# FPSModule.net
KiCad netlist of a schematic drawn in Altium Designer
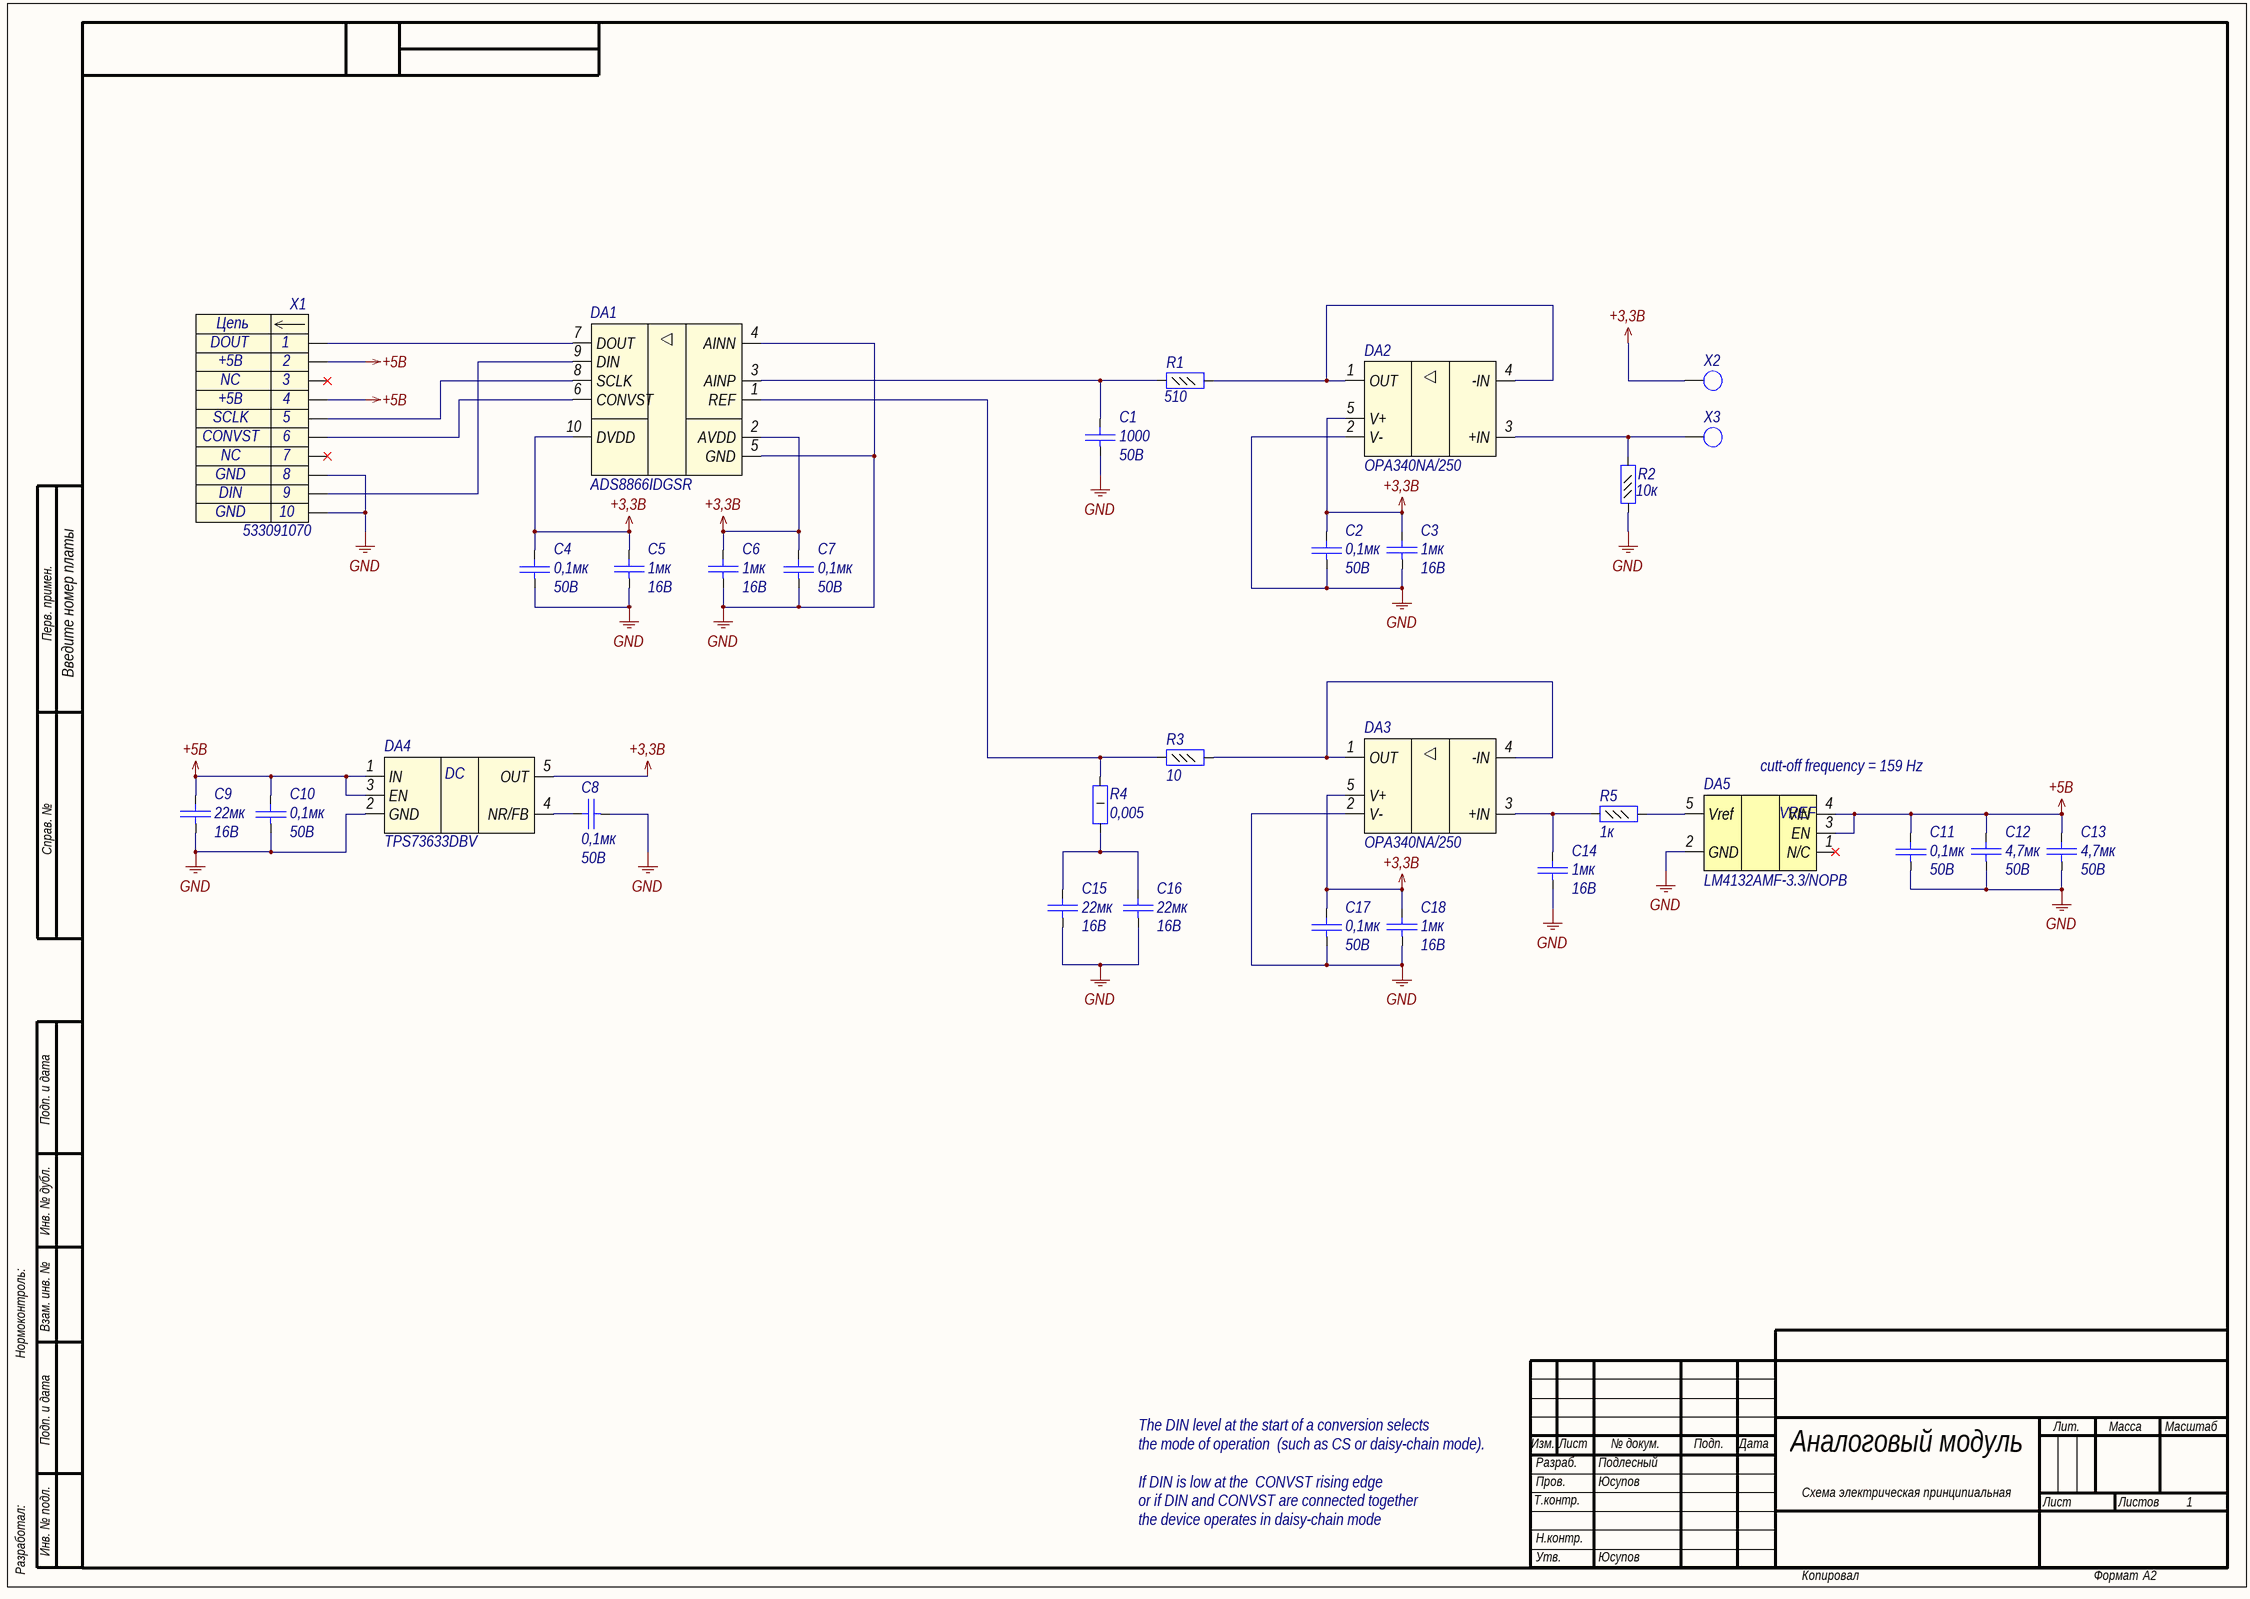
[diagram p0: FPSModule.SchDoc]

(export (version "E")
  (design (tool "Eeschema 10.0.6"))
  (components
    (comp (ref "C1")
      (value "1000")
      (footprint "C0402")
      (description "Конденсатор")
      (fields (field (name "VOLTAGE") "50B") (field (name "PART NUMBER") "GRM1555C1H102J"))
      (libsource (lib "MOP44") (part "Capacitor"))
    )
    (comp (ref "C2")
      (value "0,1мк")
      (footprint "C0402")
      (description "Конденсатор")
      (fields (field (name "VOLTAGE") "50В") (field (name "PART NUMBER") "GRM155R71H104KE14D "))
      (libsource (lib "MOP44") (part "Capacitor"))
    )
    (comp (ref "C3")
      (value "1мк")
      (footprint "C0603")
      (description "Конденсатор")
      (fields (field (name "VOLTAGE") "16B") (field (name "PART NUMBER") "GRM188R71C105KA12D**"))
      (libsource (lib "MOP44") (part "Capacitor"))
    )
    (comp (ref "C4")
      (value "0,1мк")
      (footprint "C0402")
      (description "Конденсатор")
      (fields (field (name "VOLTAGE") "50В") (field (name "PART NUMBER") "GRM155R71H104KE14D "))
      (libsource (lib "MOP44") (part "Capacitor"))
    )
    (comp (ref "C5")
      (value "1мк")
      (footprint "C0603")
      (description "Конденсатор")
      (fields (field (name "VOLTAGE") "16B") (field (name "PART NUMBER") "GRM188R71C105KA12D**"))
      (libsource (lib "MOP44") (part "Capacitor"))
    )
    (comp (ref "C6")
      (value "1мк")
      (footprint "C0603")
      (description "Конденсатор")
      (fields (field (name "VOLTAGE") "16B") (field (name "PART NUMBER") "GRM188R71C105KA12D**"))
      (libsource (lib "MOP44") (part "Capacitor"))
    )
    (comp (ref "C7")
      (value "0,1мк")
      (footprint "C0402")
      (description "Конденсатор")
      (fields (field (name "VOLTAGE") "50В") (field (name "PART NUMBER") "GRM155R71H104KE14D "))
      (libsource (lib "MOP44") (part "Capacitor"))
    )
    (comp (ref "C8")
      (value "0,1мк")
      (footprint "C0402")
      (description "Конденсатор")
      (fields (field (name "VOLTAGE") "50В") (field (name "PART NUMBER") "GRM155R71H104KE14D "))
      (libsource (lib "MOP44") (part "Capacitor"))
    )
    (comp (ref "C9")
      (value "22мк")
      (footprint "C1210")
      (description "Конденсатор")
      (fields (field (name "VOLTAGE") "16B") (field (name "PART NUMBER") "C3225X7R1C226M"))
      (libsource (lib "MOP44") (part "Capacitor"))
    )
    (comp (ref "C10")
      (value "0,1мк")
      (footprint "C0402")
      (description "Конденсатор")
      (fields (field (name "VOLTAGE") "50В") (field (name "PART NUMBER") "GRM155R71H104KE14D "))
      (libsource (lib "MOP44") (part "Capacitor"))
    )
    (comp (ref "C11")
      (value "0,1мк")
      (footprint "C0402")
      (description "Конденсатор")
      (fields (field (name "VOLTAGE") "50В") (field (name "PART NUMBER") "GRM155R71H104KE14D "))
      (libsource (lib "MOP44") (part "Capacitor"))
    )
    (comp (ref "C12")
      (value "4,7мк")
      (footprint "C0805")
      (description "Конденсатор")
      (fields (field (name "VOLTAGE") "50В") (field (name "PART NUMBER") "GRM21BZ71H475KE15L"))
      (libsource (lib "MOP44") (part "Capacitor"))
    )
    (comp (ref "C13")
      (value "4,7мк")
      (footprint "C0805")
      (description "Конденсатор")
      (fields (field (name "VOLTAGE") "50В") (field (name "PART NUMBER") "GRM21BZ71H475KE15L"))
      (libsource (lib "MOP44") (part "Capacitor"))
    )
    (comp (ref "C14")
      (value "1мк")
      (footprint "C0603")
      (description "Конденсатор")
      (fields (field (name "VOLTAGE") "16B") (field (name "PART NUMBER") "GRM188R71C105KA12D**"))
      (libsource (lib "MOP44") (part "Capacitor"))
    )
    (comp (ref "C15")
      (value "22мк")
      (footprint "C1210")
      (description "Конденсатор")
      (fields (field (name "VOLTAGE") "16B") (field (name "PART NUMBER") "C3225X7R1C226M"))
      (libsource (lib "MOP44") (part "Capacitor"))
    )
    (comp (ref "C16")
      (value "22мк")
      (footprint "C1210")
      (description "Конденсатор")
      (fields (field (name "VOLTAGE") "16B") (field (name "PART NUMBER") "C3225X7R1C226M"))
      (libsource (lib "MOP44") (part "Capacitor"))
    )
    (comp (ref "C17")
      (value "0,1мк")
      (footprint "C0402")
      (description "Конденсатор")
      (fields (field (name "VOLTAGE") "50В") (field (name "PART NUMBER") "GRM155R71H104KE14D "))
      (libsource (lib "MOP44") (part "Capacitor"))
    )
    (comp (ref "C18")
      (value "1мк")
      (footprint "C0603")
      (description "Конденсатор")
      (fields (field (name "VOLTAGE") "16B") (field (name "PART NUMBER") "GRM188R71C105KA12D**"))
      (libsource (lib "MOP44") (part "Capacitor"))
    )
    (comp (ref "DA1")
      (value "ADS8866")
      (footprint "MSOP10")
      (description "100-kSPS, serial interface, micropower, miniature,  single-ended input, SAR")
      (fields (field (name "PART NUMBER") "ADS8866IDGSR"))
      (libsource (lib "MOP44") (part "ADS8866"))
    )
    (comp (ref "DA2")
      (value "OPA340")
      (footprint "SOT23-5")
      (description "Operational Amplifiers\r\nMicroAmplifier")
      (fields (field (name "PART NUMBER") "OPA340NA/250"))
      (libsource (lib "MOP44") (part "OPA340"))
    )
    (comp (ref "DA3")
      (value "OPA340")
      (footprint "SOT23-5")
      (description "Operational Amplifiers\r\nMicroAmplifier")
      (fields (field (name "PART NUMBER") "OPA340NA/250"))
      (libsource (lib "MOP44") (part "OPA340"))
    )
    (comp (ref "DA4")
      (value "TPS736DBV")
      (footprint "SOT23-5")
      (description "400-mA Low-Dropout Regulator with Reverse Current  Protection")
      (fields (field (name "PART NUMBER") "TPS73633DBV") (field (name "MANUFACTURER") "Texas Instruments"))
      (libsource (lib "MOP44") (part "TPS736DBV"))
    )
    (comp (ref "DA5")
      (value "LM4132")
      (footprint "SOT23-5")
      (description "Precision Low Dropout Voltage Reference")
      (fields
        (field (name "PART NUMBER") "LM4132AMF-3.3/NOPB")
        (field (name "MANUFACTURER") "Texas Instruments")
      )
      (libsource (lib "MOP44") (part "LM4132"))
    )
    (comp (ref "R1")
      (value "510")
      (footprint "R0402")
      (description "Резистор")
      (fields (field (name "PART NUMBER") "RC0402FR-07510RL") (field (name "POWER") "0,062Вт"))
      (libsource (lib "MOP44") (part "Resistor_0,062Вт"))
    )
    (comp (ref "R2")
      (value "10к")
      (footprint "R0402")
      (description "Резистор")
      (fields (field (name "PART NUMBER") "RC0402FR-0710KL") (field (name "POWER") "0,062Вт"))
      (libsource (lib "") (part "Resistor_0,062Вт_1"))
    )
    (comp (ref "R3")
      (value "10")
      (footprint "R0402")
      (description "Резистор")
      (fields (field (name "PART NUMBER") "RC0402FR-0710RL") (field (name "POWER") "0,062Вт"))
      (libsource (lib "MOP44") (part "Resistor_0,062Вт"))
    )
    (comp (ref "R4")
      (value "0,005")
      (footprint "R1206")
      (description "Резистор")
      (fields (field (name "PART NUMBER") "CSRF1206FT5L00") (field (name "POWER") "1Вт"))
      (libsource (lib "MOP44") (part "Resistor_1Вт"))
    )
    (comp (ref "R5")
      (value "1к")
      (footprint "R0402")
      (description "Резистор")
      (fields (field (name "PART NUMBER") "RC0402FR-071KL") (field (name "POWER") "0,062Вт"))
      (libsource (lib "MOP44") (part "Resistor_0,062Вт"))
    )
    (comp (ref "X1")
      (value "Header_10_plg")
      (footprint "SlimStack-10pin-angl-plg")
      (description "Разъем - 10 конт. вилка")
      (fields (field (name "PART NUMBER") "533091070"))
      (libsource (lib "MOP44") (part "Header_10_plg"))
    )
    (comp (ref "X2") (value "SoldPoint") (footprint "SOLD_1PAD") (libsource (lib "MOP44") (part "SoldPoint")))
    (comp (ref "X3") (value "SoldPoint") (footprint "SOLD_1PAD") (libsource (lib "MOP44") (part "SoldPoint")))
  )
  (nets
    (net (code "1") (name "+3,3B") (class "Default")
      (node (ref "C17") (pin "2") (pinfunction "2_2") (pintype "passive"))
      (node (ref "C18") (pin "2") (pinfunction "2_2") (pintype "passive"))
      (node (ref "C2") (pin "2") (pinfunction "2_2") (pintype "passive"))
      (node (ref "C3") (pin "2") (pinfunction "2_2") (pintype "passive"))
      (node (ref "C4") (pin "2") (pinfunction "2_2") (pintype "passive"))
      (node (ref "C5") (pin "2") (pinfunction "2_2") (pintype "passive"))
      (node (ref "C6") (pin "2") (pinfunction "2_2") (pintype "passive"))
      (node (ref "C7") (pin "2") (pinfunction "2_2") (pintype "passive"))
      (node (ref "DA1") (pin "10") (pinfunction "DVDD_10") (pintype "passive"))
      (node (ref "DA1") (pin "2") (pinfunction "AVDD_2") (pintype "passive"))
      (node (ref "DA2") (pin "5") (pinfunction "V+_5") (pintype "passive"))
      (node (ref "DA3") (pin "5") (pinfunction "V+_5") (pintype "passive"))
      (node (ref "DA4") (pin "5") (pinfunction "OUT_5") (pintype "power_in"))
      (node (ref "X2") (pin "1") (pinfunction "1_1") (pintype "passive"))
    )
    (net (code "2") (name "+5B") (class "Default")
      (node (ref "C10") (pin "2") (pinfunction "2_2") (pintype "passive"))
      (node (ref "C11") (pin "2") (pinfunction "2_2") (pintype "passive"))
      (node (ref "C12") (pin "2") (pinfunction "2_2") (pintype "passive"))
      (node (ref "C13") (pin "2") (pinfunction "2_2") (pintype "passive"))
      (node (ref "C9") (pin "2") (pinfunction "2_2") (pintype "passive"))
      (node (ref "DA4") (pin "1") (pinfunction "IN_1") (pintype "power_in"))
      (node (ref "DA4") (pin "3") (pinfunction "EN_3") (pintype "power_in"))
      (node (ref "DA5") (pin "3") (pinfunction "EN_3") (pintype "passive"))
      (node (ref "DA5") (pin "4") (pinfunction "VIN_4") (pintype "passive"))
      (node (ref "X1") (pin "2") (pinfunction "2_2") (pintype "passive"))
      (node (ref "X1") (pin "4") (pinfunction "4_4") (pintype "passive"))
    )
    (net (code "3") (name "GND") (class "Default")
      (node (ref "C1") (pin "1") (pinfunction "1_1") (pintype "passive"))
      (node (ref "C10") (pin "1") (pinfunction "1_1") (pintype "passive"))
      (node (ref "C11") (pin "1") (pinfunction "1_1") (pintype "passive"))
      (node (ref "C12") (pin "1") (pinfunction "1_1") (pintype "passive"))
      (node (ref "C13") (pin "1") (pinfunction "1_1") (pintype "passive"))
      (node (ref "C14") (pin "1") (pinfunction "1_1") (pintype "passive"))
      (node (ref "C15") (pin "1") (pinfunction "1_1") (pintype "passive"))
      (node (ref "C16") (pin "1") (pinfunction "1_1") (pintype "passive"))
      (node (ref "C17") (pin "1") (pinfunction "1_1") (pintype "passive"))
      (node (ref "C18") (pin "1") (pinfunction "1_1") (pintype "passive"))
      (node (ref "C2") (pin "1") (pinfunction "1_1") (pintype "passive"))
      (node (ref "C3") (pin "1") (pinfunction "1_1") (pintype "passive"))
      (node (ref "C4") (pin "1") (pinfunction "1_1") (pintype "passive"))
      (node (ref "C5") (pin "1") (pinfunction "1_1") (pintype "passive"))
      (node (ref "C6") (pin "1") (pinfunction "1_1") (pintype "passive"))
      (node (ref "C7") (pin "1") (pinfunction "1_1") (pintype "passive"))
      (node (ref "C8") (pin "1") (pinfunction "1_1") (pintype "passive"))
      (node (ref "C9") (pin "1") (pinfunction "1_1") (pintype "passive"))
      (node (ref "DA1") (pin "4") (pinfunction "AINN_4") (pintype "passive"))
      (node (ref "DA1") (pin "5") (pinfunction "GND_5") (pintype "passive"))
      (node (ref "DA2") (pin "2") (pinfunction "V-_2") (pintype "passive"))
      (node (ref "DA3") (pin "2") (pinfunction "V-_2") (pintype "passive"))
      (node (ref "DA4") (pin "2") (pinfunction "GND_2") (pintype "power_in"))
      (node (ref "DA5") (pin "2") (pinfunction "GND_2") (pintype "passive"))
      (node (ref "R2") (pin "1") (pinfunction "1_1") (pintype "passive"))
      (node (ref "X1") (pin "10") (pinfunction "10_10") (pintype "passive"))
      (node (ref "X1") (pin "8") (pinfunction "8_8") (pintype "passive"))
    )
    (net (code "4") (name "Net-(C15-Pad2)") (class "Default")
      (node (ref "C15") (pin "2") (pinfunction "2_2") (pintype "passive"))
      (node (ref "C16") (pin "2") (pinfunction "2_2") (pintype "passive"))
      (node (ref "R4") (pin "1") (pinfunction "1_1") (pintype "passive"))
    )
    (net (code "5") (name "Net-(DA1-AINP)") (class "Default")
      (node (ref "C1") (pin "2") (pinfunction "2_2") (pintype "passive"))
      (node (ref "DA1") (pin "3") (pinfunction "AINP_3") (pintype "passive"))
      (node (ref "R1") (pin "1") (pinfunction "1_1") (pintype "passive"))
    )
    (net (code "6") (name "Net-(DA1-CONVST)") (class "Default")
      (node (ref "DA1") (pin "6") (pinfunction "CONVST_6") (pintype "passive"))
      (node (ref "X1") (pin "6") (pinfunction "6_6") (pintype "passive"))
    )
    (net (code "7") (name "Net-(DA1-DIN)") (class "Default")
      (node (ref "DA1") (pin "9") (pinfunction "DIN_9") (pintype "passive"))
      (node (ref "X1") (pin "9") (pinfunction "9_9") (pintype "passive"))
    )
    (net (code "8") (name "Net-(DA1-DOUT)") (class "Default")
      (node (ref "DA1") (pin "7") (pinfunction "DOUT_7") (pintype "passive"))
      (node (ref "X1") (pin "1") (pinfunction "1_1") (pintype "passive"))
    )
    (net (code "9") (name "Net-(DA1-REF)") (class "Default")
      (node (ref "DA1") (pin "1") (pinfunction "REF_1") (pintype "passive"))
      (node (ref "R3") (pin "1") (pinfunction "1_1") (pintype "passive"))
      (node (ref "R4") (pin "2") (pinfunction "5_2") (pintype "passive"))
    )
    (net (code "10") (name "Net-(DA1-SCLK)") (class "Default")
      (node (ref "DA1") (pin "8") (pinfunction "SCLK_8") (pintype "passive"))
      (node (ref "X1") (pin "5") (pinfunction "5_5") (pintype "passive"))
    )
    (net (code "11") (name "Net-(DA2-+IN)") (class "Default")
      (node (ref "DA2") (pin "3") (pinfunction "+IN_3") (pintype "passive"))
      (node (ref "R2") (pin "2") (pinfunction "2_2") (pintype "passive"))
      (node (ref "X3") (pin "1") (pinfunction "1_1") (pintype "passive"))
    )
    (net (code "12") (name "Net-(DA2--IN)") (class "Default")
      (node (ref "DA2") (pin "1") (pinfunction "OUT_1") (pintype "passive"))
      (node (ref "DA2") (pin "4") (pinfunction "-IN_4") (pintype "passive"))
      (node (ref "R1") (pin "2") (pinfunction "2_2") (pintype "passive"))
    )
    (net (code "13") (name "Net-(DA3-+IN)") (class "Default")
      (node (ref "C14") (pin "2") (pinfunction "2_2") (pintype "passive"))
      (node (ref "DA3") (pin "3") (pinfunction "+IN_3") (pintype "passive"))
      (node (ref "R5") (pin "1") (pinfunction "1_1") (pintype "passive"))
    )
    (net (code "14") (name "Net-(DA3--IN)") (class "Default")
      (node (ref "DA3") (pin "1") (pinfunction "OUT_1") (pintype "passive"))
      (node (ref "DA3") (pin "4") (pinfunction "-IN_4") (pintype "passive"))
      (node (ref "R3") (pin "2") (pinfunction "2_2") (pintype "passive"))
    )
    (net (code "15") (name "Net-(DA4-NR{slash}FB)") (class "Default")
      (node (ref "C8") (pin "2") (pinfunction "2_2") (pintype "passive"))
      (node (ref "DA4") (pin "4") (pinfunction "NR/FB_4") (pintype "power_in"))
    )
    (net (code "16") (name "Net-(DA5-Vref)") (class "Default")
      (node (ref "DA5") (pin "5") (pinfunction "Vref_5") (pintype "passive"))
      (node (ref "R5") (pin "2") (pinfunction "2_2") (pintype "passive"))
    )
    (net (code "17") (name "unconnected-(DA5-N{slash}C-Pad1)") (class "Default")
      (node (ref "DA5") (pin "1") (pinfunction "N/C_1") (pintype "passive+no_connect"))
    )
    (net (code "18") (name "unconnected-(X1-Pad3)") (class "Default")
      (node (ref "X1") (pin "3") (pinfunction "3_3") (pintype "passive+no_connect"))
    )
    (net (code "19") (name "unconnected-(X1-Pad7)") (class "Default")
      (node (ref "X1") (pin "7") (pinfunction "7_7") (pintype "passive+no_connect"))
    )
  )
)
